# Deadlock_Prevention_Circuit.net
KiCad netlist of a schematic drawn in EAGLE
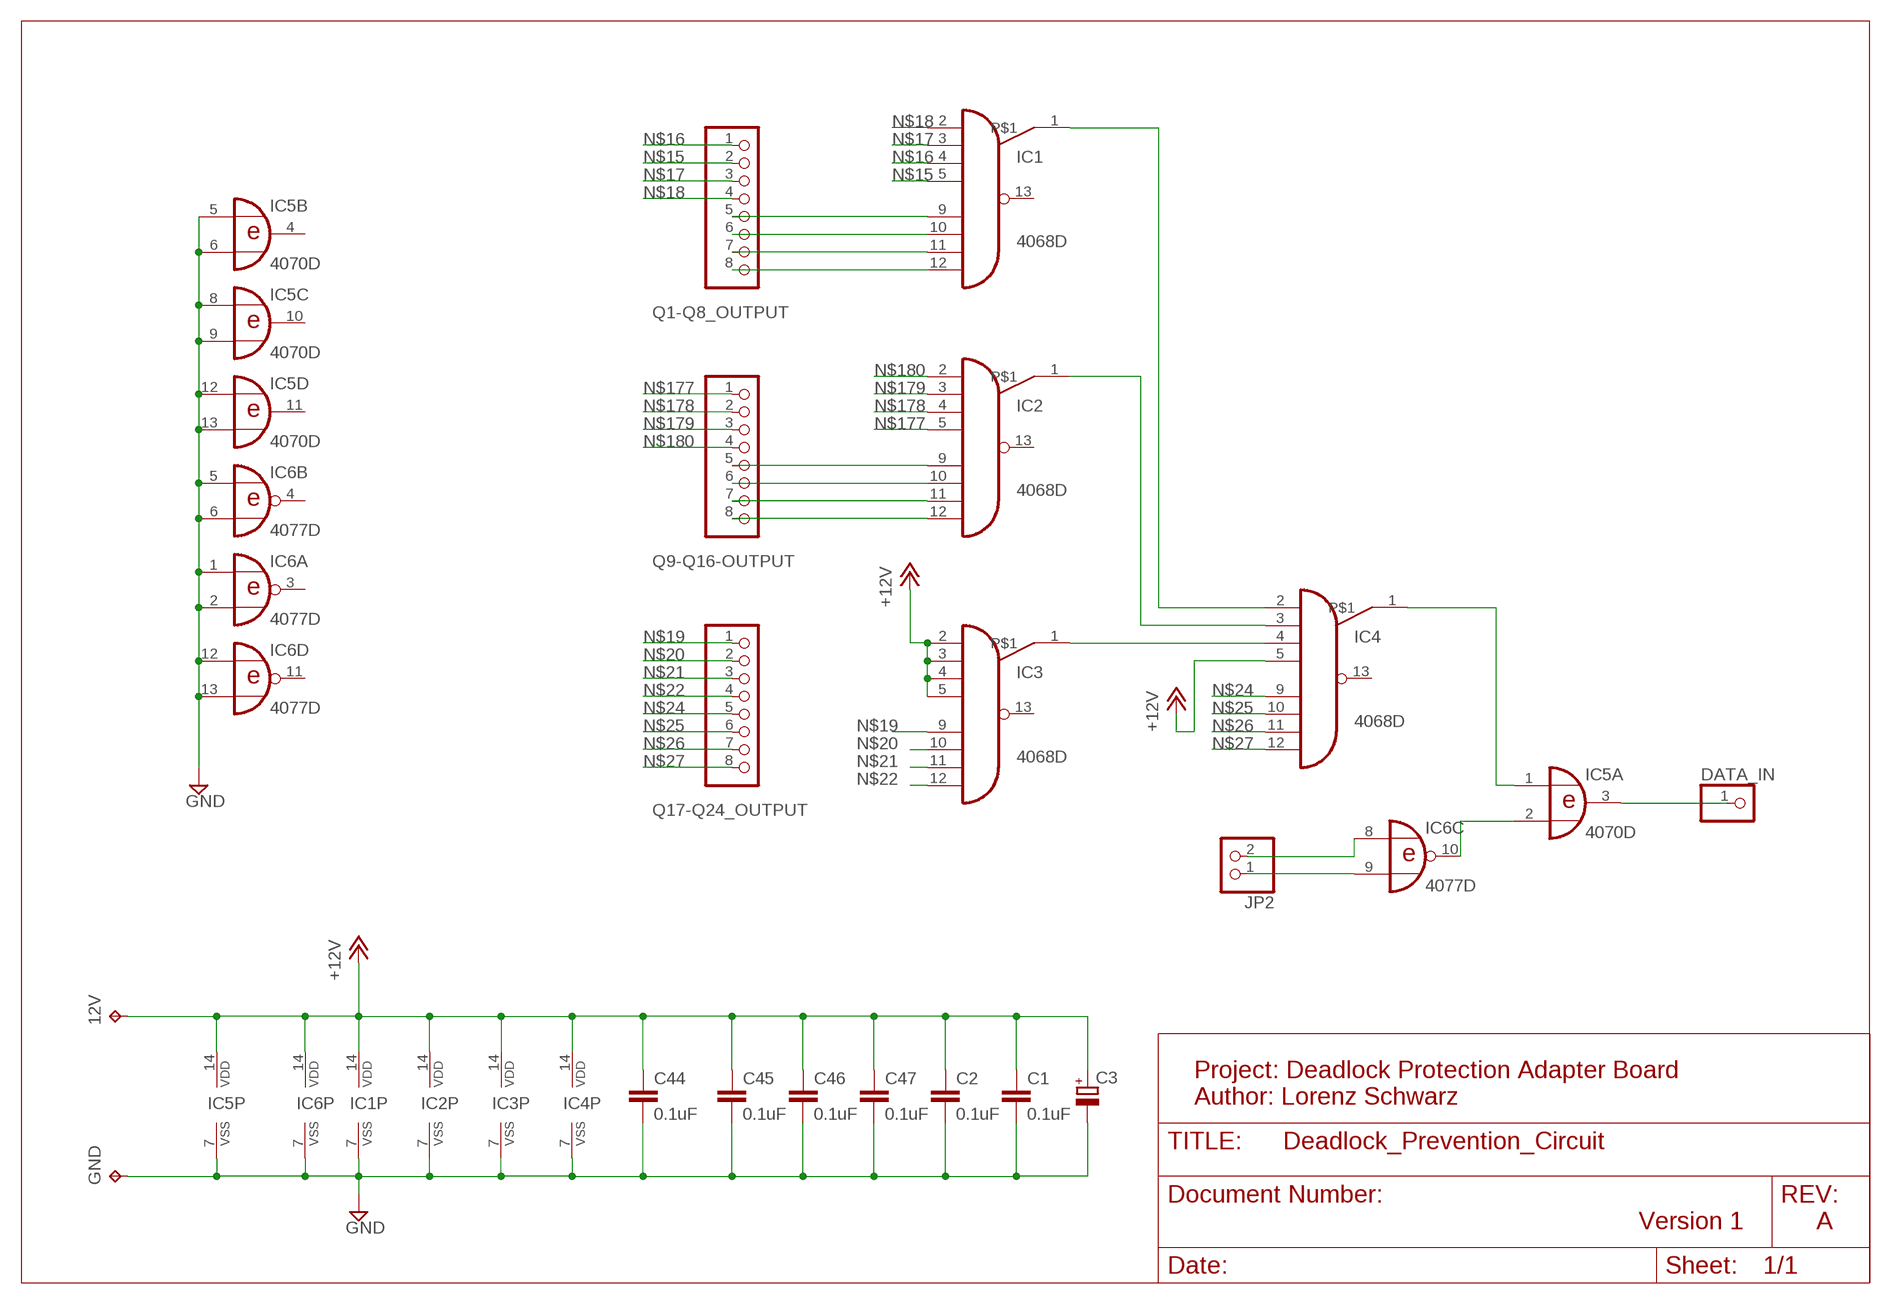
[diagram p0: schematic, sheet 1]

(export (version "E")
  (design (tool "Eeschema 10.0.6"))
  (components
    (comp (ref "12V")
      (value "TPTP15SQ")
      (footprint "eagle-import:TP15SQ")
      (libsource (lib "eagle-import") (part "TPTP15SQ"))
    )
    (comp (ref "C1")
      (value "0.1uF")
      (footprint "eagle-import:C0805")
      (libsource (lib "eagle-import") (part "C-EUC0805"))
    )
    (comp (ref "C2")
      (value "0.1uF")
      (footprint "eagle-import:C0805")
      (libsource (lib "eagle-import") (part "C-EUC0805"))
    )
    (comp (ref "C3")
      (value "CPOL-EUD")
      (footprint "eagle-import:PANASONIC_D")
      (libsource (lib "eagle-import") (part "CPOL-EUD"))
    )
    (comp (ref "C44")
      (value "0.1uF")
      (footprint "eagle-import:C0805")
      (libsource (lib "eagle-import") (part "C-EUC0805"))
    )
    (comp (ref "C45")
      (value "0.1uF")
      (footprint "eagle-import:C0805")
      (libsource (lib "eagle-import") (part "C-EUC0805"))
    )
    (comp (ref "C46")
      (value "0.1uF")
      (footprint "eagle-import:C0805")
      (libsource (lib "eagle-import") (part "C-EUC0805"))
    )
    (comp (ref "C47")
      (value "0.1uF")
      (footprint "eagle-import:C0805")
      (libsource (lib "eagle-import") (part "C-EUC0805"))
    )
    (comp (ref "DATA_IN")
      (value "PINHD-1X1")
      (footprint "eagle-import:1X01")
      (libsource (lib "eagle-import") (part "PINHD-1X1"))
    )
    (comp (ref "GND")
      (value "TPTP15SQ")
      (footprint "eagle-import:TP15SQ")
      (libsource (lib "eagle-import") (part "TPTP15SQ"))
    )
    (comp (ref "IC1")
      (value "4068D")
      (footprint "eagle-import:SO14")
      (libsource (lib "eagle-import") (part "4068D"))
    )
    (comp (ref "IC2")
      (value "4068D")
      (footprint "eagle-import:SO14")
      (libsource (lib "eagle-import") (part "4068D"))
    )
    (comp (ref "IC3")
      (value "4068D")
      (footprint "eagle-import:SO14")
      (libsource (lib "eagle-import") (part "4068D"))
    )
    (comp (ref "IC4")
      (value "4068D")
      (footprint "eagle-import:SO14")
      (libsource (lib "eagle-import") (part "4068D"))
    )
    (comp (ref "IC5")
      (value "4070D")
      (footprint "eagle-import:SO14")
      (libsource (lib "eagle-import") (part "4070D"))
    )
    (comp (ref "IC6")
      (value "4077D")
      (footprint "eagle-import:SO14")
      (libsource (lib "eagle-import") (part "4077D"))
    )
    (comp (ref "JP2")
      (value "PINHD-1X2")
      (footprint "eagle-import:1X02")
      (libsource (lib "eagle-import") (part "PINHD-1X2"))
    )
    (comp (ref "Q1-Q8_OUTPUT")
      (value "PINHD-1X8")
      (footprint "eagle-import:1X08")
      (libsource (lib "eagle-import") (part "PINHD-1X8"))
    )
    (comp (ref "Q9-Q16-OUTPUT")
      (value "PINHD-1X8")
      (footprint "eagle-import:1X08")
      (libsource (lib "eagle-import") (part "PINHD-1X8"))
    )
    (comp (ref "Q17-Q24_OUTPUT")
      (value "PINHD-1X8")
      (footprint "eagle-import:1X08")
      (libsource (lib "eagle-import") (part "PINHD-1X8"))
    )
  )
  (nets
    (net (code "1") (name "+12V") (class "Default")
      (node (ref "12V") (pin "TP") (pinfunction "TP_TP") (pintype "input"))
      (node (ref "C1") (pin "1") (pinfunction "1_1") (pintype "passive"))
      (node (ref "C2") (pin "1") (pinfunction "1_1") (pintype "passive"))
      (node (ref "C3") (pin "+") (pinfunction "+_+") (pintype "passive"))
      (node (ref "C44") (pin "1") (pinfunction "1_1") (pintype "passive"))
      (node (ref "C45") (pin "1") (pinfunction "1_1") (pintype "passive"))
      (node (ref "C46") (pin "1") (pinfunction "1_1") (pintype "passive"))
      (node (ref "C47") (pin "1") (pinfunction "1_1") (pintype "passive"))
      (node (ref "IC1") (pin "14") (pinfunction "VDD_14") (pintype "power_in"))
      (node (ref "IC2") (pin "14") (pinfunction "VDD_14") (pintype "power_in"))
      (node (ref "IC3") (pin "14") (pinfunction "VDD_14") (pintype "power_in"))
      (node (ref "IC3") (pin "2") (pinfunction "I0_2") (pintype "input"))
      (node (ref "IC3") (pin "3") (pinfunction "I1_3") (pintype "input"))
      (node (ref "IC3") (pin "4") (pinfunction "I2_4") (pintype "input"))
      (node (ref "IC3") (pin "5") (pinfunction "I3_5") (pintype "input"))
      (node (ref "IC4") (pin "14") (pinfunction "VDD_14") (pintype "power_in"))
      (node (ref "IC4") (pin "5") (pinfunction "I3_5") (pintype "input"))
      (node (ref "IC5") (pin "14") (pinfunction "VDD_14") (pintype "power_in"))
      (node (ref "IC6") (pin "14") (pinfunction "VDD_14") (pintype "power_in"))
    )
    (net (code "2") (name "/N$15") (class "Default")
      (node (ref "IC1") (pin "5") (pinfunction "I3_5") (pintype "input"))
      (node (ref "Q1-Q8_OUTPUT") (pin "2") (pinfunction "2_2") (pintype "passive"))
    )
    (net (code "3") (name "/N$16") (class "Default")
      (node (ref "IC1") (pin "4") (pinfunction "I2_4") (pintype "input"))
      (node (ref "Q1-Q8_OUTPUT") (pin "1") (pinfunction "1_1") (pintype "passive"))
    )
    (net (code "4") (name "/N$17") (class "Default")
      (node (ref "IC1") (pin "3") (pinfunction "I1_3") (pintype "input"))
      (node (ref "Q1-Q8_OUTPUT") (pin "3") (pinfunction "3_3") (pintype "passive"))
    )
    (net (code "5") (name "/N$18") (class "Default")
      (node (ref "IC1") (pin "2") (pinfunction "I0_2") (pintype "input"))
      (node (ref "Q1-Q8_OUTPUT") (pin "4") (pinfunction "4_4") (pintype "passive"))
    )
    (net (code "6") (name "/N$19") (class "Default")
      (node (ref "IC3") (pin "9") (pinfunction "I4_9") (pintype "input"))
      (node (ref "Q17-Q24_OUTPUT") (pin "1") (pinfunction "1_1") (pintype "passive"))
    )
    (net (code "7") (name "/N$20") (class "Default")
      (node (ref "IC3") (pin "10") (pinfunction "I5_10") (pintype "input"))
      (node (ref "Q17-Q24_OUTPUT") (pin "2") (pinfunction "2_2") (pintype "passive"))
    )
    (net (code "8") (name "/N$21") (class "Default")
      (node (ref "IC3") (pin "11") (pinfunction "I6_11") (pintype "input"))
      (node (ref "Q17-Q24_OUTPUT") (pin "3") (pinfunction "3_3") (pintype "passive"))
    )
    (net (code "9") (name "/N$22") (class "Default")
      (node (ref "IC3") (pin "12") (pinfunction "I7_12") (pintype "input"))
      (node (ref "Q17-Q24_OUTPUT") (pin "4") (pinfunction "4_4") (pintype "passive"))
    )
    (net (code "10") (name "/N$24") (class "Default")
      (node (ref "IC4") (pin "9") (pinfunction "I4_9") (pintype "input"))
      (node (ref "Q17-Q24_OUTPUT") (pin "5") (pinfunction "5_5") (pintype "passive"))
    )
    (net (code "11") (name "/N$25") (class "Default")
      (node (ref "IC4") (pin "10") (pinfunction "I5_10") (pintype "input"))
      (node (ref "Q17-Q24_OUTPUT") (pin "6") (pinfunction "6_6") (pintype "passive"))
    )
    (net (code "12") (name "/N$26") (class "Default")
      (node (ref "IC4") (pin "11") (pinfunction "I6_11") (pintype "input"))
      (node (ref "Q17-Q24_OUTPUT") (pin "7") (pinfunction "7_7") (pintype "passive"))
    )
    (net (code "13") (name "/N$27") (class "Default")
      (node (ref "IC4") (pin "12") (pinfunction "I7_12") (pintype "input"))
      (node (ref "Q17-Q24_OUTPUT") (pin "8") (pinfunction "8_8") (pintype "passive"))
    )
    (net (code "14") (name "/N$177") (class "Default")
      (node (ref "IC2") (pin "5") (pinfunction "I3_5") (pintype "input"))
      (node (ref "Q9-Q16-OUTPUT") (pin "1") (pinfunction "1_1") (pintype "passive"))
    )
    (net (code "15") (name "/N$178") (class "Default")
      (node (ref "IC2") (pin "4") (pinfunction "I2_4") (pintype "input"))
      (node (ref "Q9-Q16-OUTPUT") (pin "2") (pinfunction "2_2") (pintype "passive"))
    )
    (net (code "16") (name "/N$179") (class "Default")
      (node (ref "IC2") (pin "3") (pinfunction "I1_3") (pintype "input"))
      (node (ref "Q9-Q16-OUTPUT") (pin "3") (pinfunction "3_3") (pintype "passive"))
    )
    (net (code "17") (name "/N$180") (class "Default")
      (node (ref "IC2") (pin "2") (pinfunction "I0_2") (pintype "input"))
      (node (ref "Q9-Q16-OUTPUT") (pin "4") (pinfunction "4_4") (pintype "passive"))
    )
    (net (code "18") (name "GND") (class "Default")
      (node (ref "C1") (pin "2") (pinfunction "2_2") (pintype "passive"))
      (node (ref "C2") (pin "2") (pinfunction "2_2") (pintype "passive"))
      (node (ref "C3") (pin "-") (pinfunction "-_-") (pintype "passive"))
      (node (ref "C44") (pin "2") (pinfunction "2_2") (pintype "passive"))
      (node (ref "C45") (pin "2") (pinfunction "2_2") (pintype "passive"))
      (node (ref "C46") (pin "2") (pinfunction "2_2") (pintype "passive"))
      (node (ref "C47") (pin "2") (pinfunction "2_2") (pintype "passive"))
      (node (ref "GND") (pin "TP") (pinfunction "TP_TP") (pintype "input"))
      (node (ref "IC1") (pin "7") (pinfunction "VSS_7") (pintype "power_in"))
      (node (ref "IC2") (pin "7") (pinfunction "VSS_7") (pintype "power_in"))
      (node (ref "IC3") (pin "7") (pinfunction "VSS_7") (pintype "power_in"))
      (node (ref "IC4") (pin "7") (pinfunction "VSS_7") (pintype "power_in"))
      (node (ref "IC5") (pin "12") (pinfunction "I0_12") (pintype "input"))
      (node (ref "IC5") (pin "13") (pinfunction "I1_13") (pintype "input"))
      (node (ref "IC5") (pin "5") (pinfunction "I0_5") (pintype "input"))
      (node (ref "IC5") (pin "6") (pinfunction "I1_6") (pintype "input"))
      (node (ref "IC5") (pin "7") (pinfunction "VSS_7") (pintype "power_in"))
      (node (ref "IC5") (pin "8") (pinfunction "I0_8") (pintype "input"))
      (node (ref "IC5") (pin "9") (pinfunction "I1_9") (pintype "input"))
      (node (ref "IC6") (pin "1") (pinfunction "I0_1") (pintype "input"))
      (node (ref "IC6") (pin "12") (pinfunction "I0_12") (pintype "input"))
      (node (ref "IC6") (pin "13") (pinfunction "I1_13") (pintype "input"))
      (node (ref "IC6") (pin "2") (pinfunction "I1_2") (pintype "input"))
      (node (ref "IC6") (pin "5") (pinfunction "I0_5") (pintype "input"))
      (node (ref "IC6") (pin "6") (pinfunction "I1_6") (pintype "input"))
      (node (ref "IC6") (pin "7") (pinfunction "VSS_7") (pintype "power_in"))
    )
    (net (code "19") (name "Net-(IC1A-I4)") (class "Default")
      (node (ref "IC1") (pin "9") (pinfunction "I4_9") (pintype "input"))
      (node (ref "Q1-Q8_OUTPUT") (pin "5") (pinfunction "5_5") (pintype "passive"))
    )
    (net (code "20") (name "Net-(IC1A-I5)") (class "Default")
      (node (ref "IC1") (pin "10") (pinfunction "I5_10") (pintype "input"))
      (node (ref "Q1-Q8_OUTPUT") (pin "6") (pinfunction "6_6") (pintype "passive"))
    )
    (net (code "21") (name "Net-(IC1A-I6)") (class "Default")
      (node (ref "IC1") (pin "11") (pinfunction "I6_11") (pintype "input"))
      (node (ref "Q1-Q8_OUTPUT") (pin "7") (pinfunction "7_7") (pintype "passive"))
    )
    (net (code "22") (name "Net-(IC1A-I7)") (class "Default")
      (node (ref "IC1") (pin "12") (pinfunction "I7_12") (pintype "input"))
      (node (ref "Q1-Q8_OUTPUT") (pin "8") (pinfunction "8_8") (pintype "passive"))
    )
    (net (code "23") (name "Net-(IC1A-P$1)") (class "Default")
      (node (ref "IC1") (pin "1") (pinfunction "P$1_1") (pintype "output"))
      (node (ref "IC4") (pin "2") (pinfunction "I0_2") (pintype "input"))
    )
    (net (code "24") (name "Net-(IC2A-I4)") (class "Default")
      (node (ref "IC2") (pin "9") (pinfunction "I4_9") (pintype "input"))
      (node (ref "Q9-Q16-OUTPUT") (pin "5") (pinfunction "5_5") (pintype "passive"))
    )
    (net (code "25") (name "Net-(IC2A-I5)") (class "Default")
      (node (ref "IC2") (pin "10") (pinfunction "I5_10") (pintype "input"))
      (node (ref "Q9-Q16-OUTPUT") (pin "6") (pinfunction "6_6") (pintype "passive"))
    )
    (net (code "26") (name "Net-(IC2A-I6)") (class "Default")
      (node (ref "IC2") (pin "11") (pinfunction "I6_11") (pintype "input"))
      (node (ref "Q9-Q16-OUTPUT") (pin "7") (pinfunction "7_7") (pintype "passive"))
    )
    (net (code "27") (name "Net-(IC2A-I7)") (class "Default")
      (node (ref "IC2") (pin "12") (pinfunction "I7_12") (pintype "input"))
      (node (ref "Q9-Q16-OUTPUT") (pin "8") (pinfunction "8_8") (pintype "passive"))
    )
    (net (code "28") (name "Net-(IC2A-P$1)") (class "Default")
      (node (ref "IC2") (pin "1") (pinfunction "P$1_1") (pintype "output"))
      (node (ref "IC4") (pin "3") (pinfunction "I1_3") (pintype "input"))
    )
    (net (code "29") (name "Net-(IC3A-P$1)") (class "Default")
      (node (ref "IC3") (pin "1") (pinfunction "P$1_1") (pintype "output"))
      (node (ref "IC4") (pin "4") (pinfunction "I2_4") (pintype "input"))
    )
    (net (code "30") (name "Net-(IC4A-P$1)") (class "Default")
      (node (ref "IC4") (pin "1") (pinfunction "P$1_1") (pintype "output"))
      (node (ref "IC5") (pin "1") (pinfunction "I0_1") (pintype "input"))
    )
    (net (code "31") (name "Net-(IC5A-I1)") (class "Default")
      (node (ref "IC5") (pin "2") (pinfunction "I1_2") (pintype "input"))
      (node (ref "IC6") (pin "10") (pinfunction "O_10") (pintype "output"))
    )
    (net (code "32") (name "Net-(IC5A-O)") (class "Default")
      (node (ref "DATA_IN") (pin "1") (pinfunction "1_1") (pintype "passive"))
      (node (ref "IC5") (pin "3") (pinfunction "O_3") (pintype "output"))
    )
    (net (code "33") (name "Net-(IC6C-I0)") (class "Default")
      (node (ref "IC6") (pin "8") (pinfunction "I0_8") (pintype "input"))
      (node (ref "JP2") (pin "2") (pinfunction "2_2") (pintype "passive"))
    )
    (net (code "34") (name "Net-(IC6C-I1)") (class "Default")
      (node (ref "IC6") (pin "9") (pinfunction "I1_9") (pintype "input"))
      (node (ref "JP2") (pin "1") (pinfunction "1_1") (pintype "passive"))
    )
    (net (code "35") (name "unconnected-(IC1A-J-Pad13)") (class "Default")
      (node (ref "IC1") (pin "13") (pinfunction "J_13") (pintype "output"))
    )
    (net (code "36") (name "unconnected-(IC2A-J-Pad13)") (class "Default")
      (node (ref "IC2") (pin "13") (pinfunction "J_13") (pintype "output"))
    )
    (net (code "37") (name "unconnected-(IC3A-J-Pad13)") (class "Default")
      (node (ref "IC3") (pin "13") (pinfunction "J_13") (pintype "output"))
    )
    (net (code "38") (name "unconnected-(IC4A-J-Pad13)") (class "Default")
      (node (ref "IC4") (pin "13") (pinfunction "J_13") (pintype "output"))
    )
    (net (code "39") (name "unconnected-(IC5B-O-Pad4)") (class "Default")
      (node (ref "IC5") (pin "4") (pinfunction "O_4") (pintype "output"))
    )
    (net (code "40") (name "unconnected-(IC5C-O-Pad10)") (class "Default")
      (node (ref "IC5") (pin "10") (pinfunction "O_10") (pintype "output"))
    )
    (net (code "41") (name "unconnected-(IC5D-O-Pad11)") (class "Default")
      (node (ref "IC5") (pin "11") (pinfunction "O_11") (pintype "output"))
    )
    (net (code "42") (name "unconnected-(IC6A-O-Pad3)") (class "Default")
      (node (ref "IC6") (pin "3") (pinfunction "O_3") (pintype "output"))
    )
    (net (code "43") (name "unconnected-(IC6B-O-Pad4)") (class "Default")
      (node (ref "IC6") (pin "4") (pinfunction "O_4") (pintype "output"))
    )
    (net (code "44") (name "unconnected-(IC6D-O-Pad11)") (class "Default")
      (node (ref "IC6") (pin "11") (pinfunction "O_11") (pintype "output"))
    )
  )
)
